# simple_rat.net
KiCad netlist of a schematic drawn in EAGLE
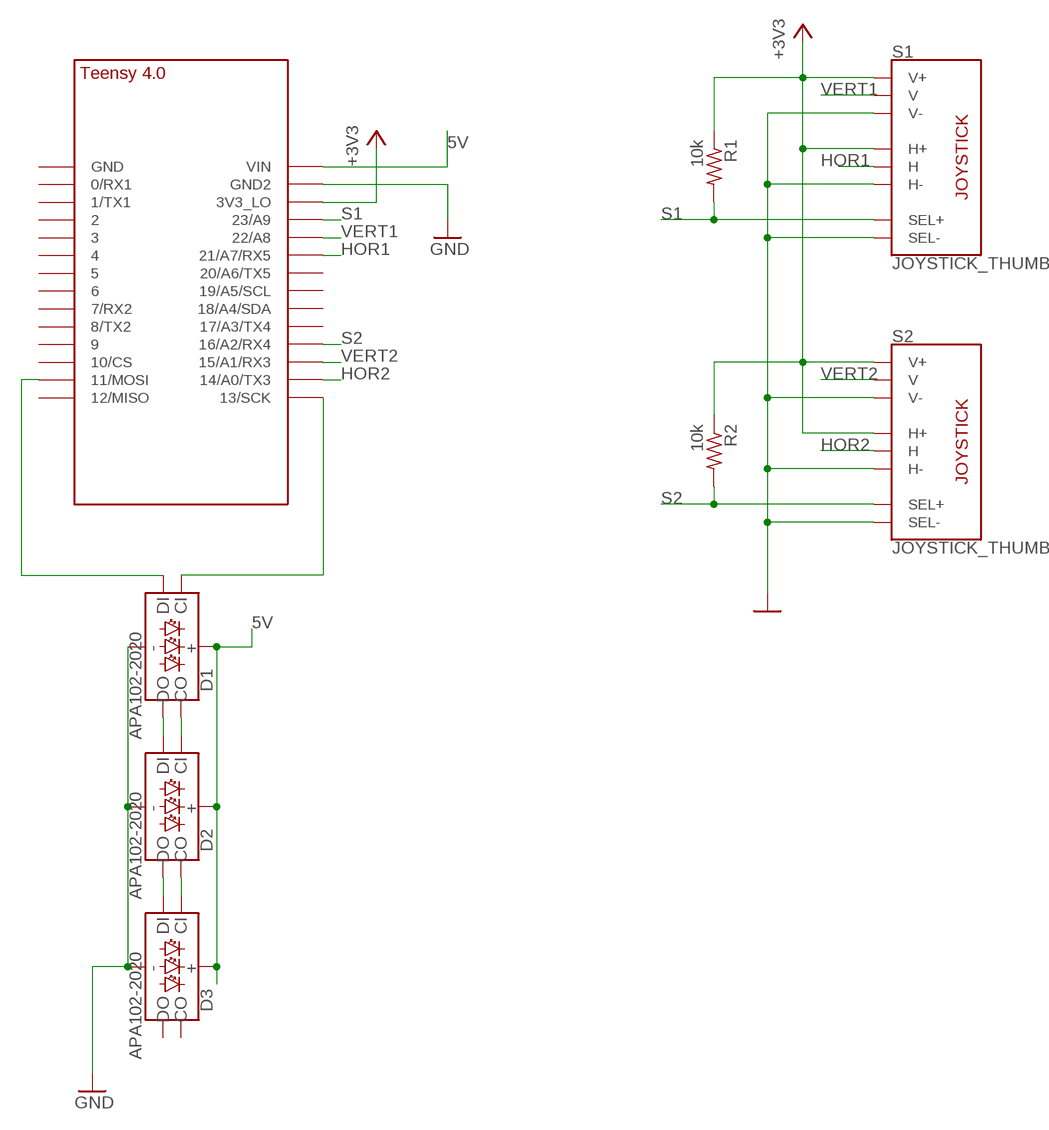
[diagram p0: schematic, sheet 1]

(export (version "E")
  (design (tool "Eeschema 10.0.6"))
  (components
    (comp (ref "D1")
      (value "APA102-2020")
      (footprint "eagle-import:APA102-2020")
      (libsource (lib "eagle-import") (part "APA102-2020"))
    )
    (comp (ref "D2")
      (value "APA102-2020")
      (footprint "eagle-import:APA102-2020")
      (libsource (lib "eagle-import") (part "APA102-2020"))
    )
    (comp (ref "D3")
      (value "APA102-2020")
      (footprint "eagle-import:APA102-2020")
      (libsource (lib "eagle-import") (part "APA102-2020"))
    )
    (comp (ref "MCU")
      (value "TEENSY_4.0-NOBOTTOM")
      (footprint "eagle-import:TEENSY_4.0-NOBOTTOM")
      (libsource (lib "eagle-import") (part "TEENSY_4.0-NOBOTTOM"))
    )
    (comp (ref "R1")
      (value "10k")
      (footprint "eagle-import:R0603")
      (libsource (lib "eagle-import") (part "R-US_R0603"))
    )
    (comp (ref "R2")
      (value "10k")
      (footprint "eagle-import:R0603")
      (libsource (lib "eagle-import") (part "R-US_R0603"))
    )
    (comp (ref "S1")
      (value "JOYSTICK_THUMB")
      (footprint "eagle-import:JOYSTICK")
      (libsource (lib "eagle-import") (part "JOYSTICK_THUMB"))
    )
    (comp (ref "S2")
      (value "JOYSTICK_THUMB")
      (footprint "eagle-import:JOYSTICK")
      (libsource (lib "eagle-import") (part "JOYSTICK_THUMB"))
    )
  )
  (nets
    (net (code "1") (name "+3V3") (class "Default")
      (node (ref "MCU") (pin "3V3_LO") (pinfunction "3V3_LO_3V3_LO") (pintype "bidirectional"))
      (node (ref "R1") (pin "1") (pinfunction "1_1") (pintype "passive"))
      (node (ref "R2") (pin "1") (pinfunction "1_1") (pintype "passive"))
      (node (ref "S1") (pin "H1") (pinfunction "H+_H1") (pintype "bidirectional"))
      (node (ref "S1") (pin "V1") (pinfunction "V+_V1") (pintype "bidirectional"))
      (node (ref "S2") (pin "H1") (pinfunction "H+_H1") (pintype "bidirectional"))
      (node (ref "S2") (pin "V1") (pinfunction "V+_V1") (pintype "bidirectional"))
    )
    (net (code "2") (name "/5V") (class "Default")
      (node (ref "D1") (pin "5V_VIA") (pinfunction "VCC_5V_VIA") (pintype "bidirectional"))
      (node (ref "D1") (pin "VDD") (pinfunction "VCC_VDD") (pintype "bidirectional"))
      (node (ref "D2") (pin "5V_VIA") (pinfunction "VCC_5V_VIA") (pintype "bidirectional"))
      (node (ref "D2") (pin "VDD") (pinfunction "VCC_VDD") (pintype "bidirectional"))
      (node (ref "D3") (pin "5V_VIA") (pinfunction "VCC_5V_VIA") (pintype "bidirectional"))
      (node (ref "D3") (pin "VDD") (pinfunction "VCC_VDD") (pintype "bidirectional"))
      (node (ref "MCU") (pin "VIN") (pinfunction "VIN_VIN") (pintype "bidirectional"))
    )
    (net (code "3") (name "/HOR1") (class "Default")
      (node (ref "MCU") (pin "21/A7") (pinfunction "21/A7/RX5_21/A7") (pintype "bidirectional"))
      (node (ref "S1") (pin "H2") (pinfunction "H_H2") (pintype "bidirectional"))
    )
    (net (code "4") (name "/HOR2") (class "Default")
      (node (ref "MCU") (pin "14/A0") (pinfunction "14/A0/TX3_14/A0") (pintype "bidirectional"))
      (node (ref "S2") (pin "H2") (pinfunction "H_H2") (pintype "bidirectional"))
    )
    (net (code "5") (name "/S1") (class "Default")
      (node (ref "MCU") (pin "23/A9") (pinfunction "23/A9_23/A9") (pintype "bidirectional"))
      (node (ref "R1") (pin "2") (pinfunction "2_2") (pintype "passive"))
      (node (ref "S1") (pin "B1A") (pinfunction "SEL+_B1A") (pintype "bidirectional"))
    )
    (net (code "6") (name "/S2") (class "Default")
      (node (ref "MCU") (pin "16/A2") (pinfunction "16/A2/RX4_16/A2") (pintype "bidirectional"))
      (node (ref "R2") (pin "2") (pinfunction "2_2") (pintype "passive"))
      (node (ref "S2") (pin "B1A") (pinfunction "SEL+_B1A") (pintype "bidirectional"))
    )
    (net (code "7") (name "/VERT1") (class "Default")
      (node (ref "MCU") (pin "22/A8") (pinfunction "22/A8_22/A8") (pintype "bidirectional"))
      (node (ref "S1") (pin "V2") (pinfunction "V_V2") (pintype "bidirectional"))
    )
    (net (code "8") (name "/VERT2") (class "Default")
      (node (ref "MCU") (pin "15/A1") (pinfunction "15/A1/RX3_15/A1") (pintype "bidirectional"))
      (node (ref "S2") (pin "V2") (pinfunction "V_V2") (pintype "bidirectional"))
    )
    (net (code "9") (name "GND") (class "Default")
      (node (ref "D1") (pin "GND") (pinfunction "GND_GND") (pintype "bidirectional"))
      (node (ref "D1") (pin "GND_VIA") (pinfunction "GND_GND_VIA") (pintype "bidirectional"))
      (node (ref "D2") (pin "GND") (pinfunction "GND_GND") (pintype "bidirectional"))
      (node (ref "D2") (pin "GND_VIA") (pinfunction "GND_GND_VIA") (pintype "bidirectional"))
      (node (ref "D3") (pin "GND") (pinfunction "GND_GND") (pintype "bidirectional"))
      (node (ref "D3") (pin "GND_VIA") (pinfunction "GND_GND_VIA") (pintype "bidirectional"))
      (node (ref "MCU") (pin "GND2") (pinfunction "GND2_GND2") (pintype "bidirectional"))
      (node (ref "S1") (pin "B2A") (pinfunction "SEL-_B2A") (pintype "bidirectional"))
      (node (ref "S1") (pin "H3") (pinfunction "H-_H3") (pintype "bidirectional"))
      (node (ref "S1") (pin "V3") (pinfunction "V-_V3") (pintype "bidirectional"))
      (node (ref "S2") (pin "B2A") (pinfunction "SEL-_B2A") (pintype "bidirectional"))
      (node (ref "S2") (pin "H3") (pinfunction "H-_H3") (pintype "bidirectional"))
      (node (ref "S2") (pin "V3") (pinfunction "V-_V3") (pintype "bidirectional"))
    )
    (net (code "10") (name "Net-(D1-CI)") (class "Default")
      (node (ref "D1") (pin "CKI") (pinfunction "CI_CKI") (pintype "bidirectional"))
      (node (ref "MCU") (pin "13/SCK") (pinfunction "13/SCK_13/SCK") (pintype "bidirectional"))
    )
    (net (code "11") (name "Net-(D1-CO)") (class "Default")
      (node (ref "D1") (pin "CKO") (pinfunction "CO_CKO") (pintype "bidirectional"))
      (node (ref "D2") (pin "CKI") (pinfunction "CI_CKI") (pintype "bidirectional"))
    )
    (net (code "12") (name "Net-(D1-DI)") (class "Default")
      (node (ref "D1") (pin "SDI") (pinfunction "DI_SDI") (pintype "bidirectional"))
      (node (ref "MCU") (pin "11/MOSI") (pinfunction "11/MOSI_11/MOSI") (pintype "bidirectional"))
    )
    (net (code "13") (name "Net-(D1-DO)") (class "Default")
      (node (ref "D1") (pin "SDO") (pinfunction "DO_SDO") (pintype "bidirectional"))
      (node (ref "D2") (pin "SDI") (pinfunction "DI_SDI") (pintype "bidirectional"))
    )
    (net (code "14") (name "Net-(D2-CO)") (class "Default")
      (node (ref "D2") (pin "CKO") (pinfunction "CO_CKO") (pintype "bidirectional"))
      (node (ref "D3") (pin "CKI") (pinfunction "CI_CKI") (pintype "bidirectional"))
    )
    (net (code "15") (name "Net-(D2-DO)") (class "Default")
      (node (ref "D2") (pin "SDO") (pinfunction "DO_SDO") (pintype "bidirectional"))
      (node (ref "D3") (pin "SDI") (pinfunction "DI_SDI") (pintype "bidirectional"))
    )
    (net (code "16") (name "unconnected-(D3-CO-PadCKO)") (class "Default")
      (node (ref "D3") (pin "CKO") (pinfunction "CO_CKO") (pintype "bidirectional"))
    )
    (net (code "17") (name "unconnected-(D3-DO-PadSDO)") (class "Default")
      (node (ref "D3") (pin "SDO") (pinfunction "DO_SDO") (pintype "bidirectional"))
    )
    (net (code "18") (name "unconnected-(MCU-0{slash}RX1-Pad0{slash}RX)") (class "Default")
      (node (ref "MCU") (pin "0/RX") (pinfunction "0/RX1_0/RX") (pintype "bidirectional"))
    )
    (net (code "19") (name "unconnected-(MCU-1{slash}TX1-Pad1{slash}TX)") (class "Default")
      (node (ref "MCU") (pin "1/TX") (pinfunction "1/TX1_1/TX") (pintype "bidirectional"))
    )
    (net (code "20") (name "unconnected-(MCU-3-Pad3{slash}CANTX)") (class "Default")
      (node (ref "MCU") (pin "3/CANTX") (pinfunction "3_3/CANTX") (pintype "bidirectional"))
    )
    (net (code "21") (name "unconnected-(MCU-4-Pad4{slash}CANRX)") (class "Default")
      (node (ref "MCU") (pin "4/CANRX") (pinfunction "4_4/CANRX") (pintype "bidirectional"))
    )
    (net (code "22") (name "unconnected-(MCU-7{slash}RX2-Pad7)") (class "Default")
      (node (ref "MCU") (pin "7") (pinfunction "7/RX2_7") (pintype "bidirectional"))
    )
    (net (code "23") (name "unconnected-(MCU-8{slash}TX2-Pad8)") (class "Default")
      (node (ref "MCU") (pin "8") (pinfunction "8/TX2_8") (pintype "bidirectional"))
    )
    (net (code "24") (name "unconnected-(MCU-9-Pad9{slash}CS)") (class "Default")
      (node (ref "MCU") (pin "9/CS") (pinfunction "9_9/CS") (pintype "bidirectional"))
    )
    (net (code "25") (name "unconnected-(MCU-17{slash}A3{slash}TX4-Pad17{slash}A3)") (class "Default")
      (node (ref "MCU") (pin "17/A3") (pinfunction "17/A3/TX4_17/A3") (pintype "bidirectional"))
    )
    (net (code "26") (name "unconnected-(MCU-20{slash}A6{slash}TX5-Pad20{slash}A6)") (class "Default")
      (node (ref "MCU") (pin "20/A6") (pinfunction "20/A6/TX5_20/A6") (pintype "bidirectional"))
    )
    (net (code "27") (name "unconnected-(MCU-Pad2)") (class "Default")
      (node (ref "MCU") (pin "2") (pinfunction "2_2") (pintype "bidirectional"))
    )
    (net (code "28") (name "unconnected-(MCU-Pad5)") (class "Default")
      (node (ref "MCU") (pin "5") (pinfunction "5_5") (pintype "bidirectional"))
    )
    (net (code "29") (name "unconnected-(MCU-Pad6)") (class "Default")
      (node (ref "MCU") (pin "6") (pinfunction "6_6") (pintype "bidirectional"))
    )
    (net (code "30") (name "unconnected-(MCU-Pad10{slash}CS)") (class "Default")
      (node (ref "MCU") (pin "10/CS") (pinfunction "10/CS_10/CS") (pintype "bidirectional"))
    )
    (net (code "31") (name "unconnected-(MCU-Pad12{slash}MISO)") (class "Default")
      (node (ref "MCU") (pin "12/MISO") (pinfunction "12/MISO_12/MISO") (pintype "bidirectional"))
    )
    (net (code "32") (name "unconnected-(MCU-Pad18{slash}A4{slash}SDA)") (class "Default")
      (node (ref "MCU") (pin "18/A4/SDA") (pinfunction "18/A4/SDA_18/A4/SDA") (pintype "bidirectional"))
    )
    (net (code "33") (name "unconnected-(MCU-Pad19{slash}A5{slash}SCL)") (class "Default")
      (node (ref "MCU") (pin "19/A5/SCL") (pinfunction "19/A5/SCL_19/A5/SCL") (pintype "bidirectional"))
    )
    (net (code "34") (name "unconnected-(MCU-PadGND)") (class "Default")
      (node (ref "MCU") (pin "GND") (pinfunction "GND_GND") (pintype "bidirectional"))
    )
  )
)
